# PiLoraGatewayV2_7.net
KiCad netlist of a schematic drawn in EAGLE
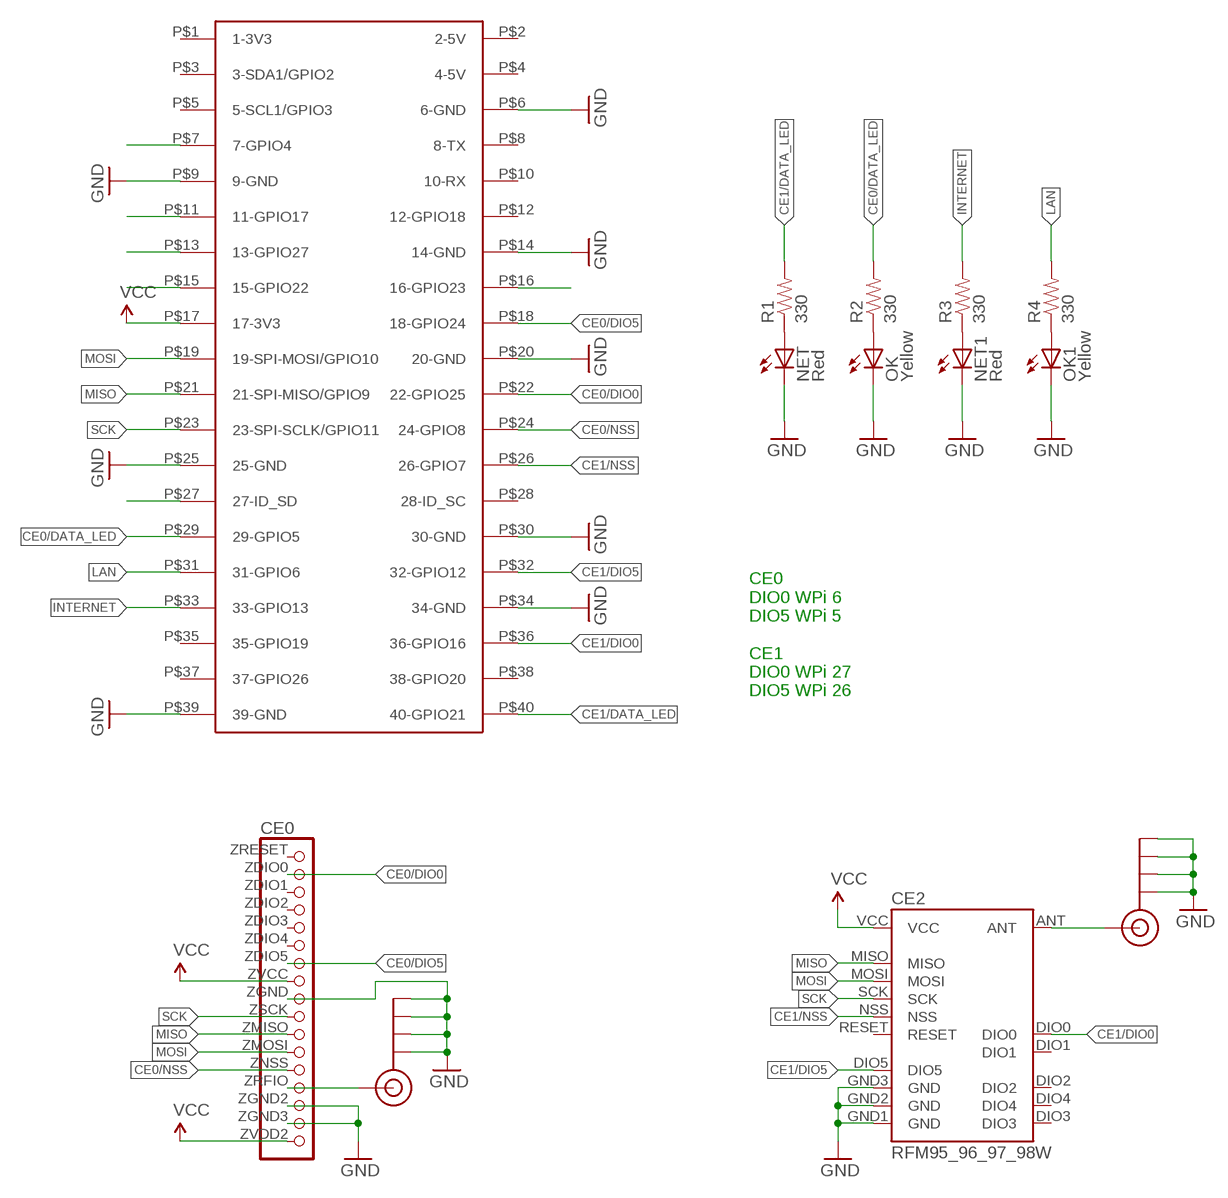
[diagram p0: schematic, sheet 1]

(export (version "E")
  (design (tool "Eeschema 10.0.6"))
  (components
    (comp (ref "CE0")
      (value "DRF1278F_BKOUTDP1276")
      (footprint "eagle-import:ANYLINK_DP1276")
      (libsource (lib "eagle-import") (part "DRF1278F_BKOUTDP1276"))
    )
    (comp (ref "CE2")
      (value "RFM95_96_97_98W")
      (footprint "eagle-import:RFM95_96_97_98W")
      (libsource (lib "eagle-import") (part "RFM95_96_97_98W"))
    )
    (comp (ref "J$1")
      (value "SMA_EDGE")
      (footprint "eagle-import:SMA-EDGE")
      (libsource (lib "eagle-import") (part "SMA_EDGE"))
    )
    (comp (ref "J$2")
      (value "SMA_EDGE")
      (footprint "eagle-import:SMA-EDGE")
      (libsource (lib "eagle-import") (part "SMA_EDGE"))
    )
    (comp (ref "NET")
      (value "Red")
      (footprint "eagle-import:LED-0603")
      (libsource (lib "eagle-import") (part "LED0603"))
    )
    (comp (ref "NET1")
      (value "Red")
      (footprint "eagle-import:LED-0603")
      (libsource (lib "eagle-import") (part "LED0603"))
    )
    (comp (ref "OK")
      (value "Yellow")
      (footprint "eagle-import:LED-0603")
      (libsource (lib "eagle-import") (part "LED0603"))
    )
    (comp (ref "OK1")
      (value "Yellow")
      (footprint "eagle-import:LED-0603")
      (libsource (lib "eagle-import") (part "LED0603"))
    )
    (comp (ref "R1")
      (value "330")
      (footprint "eagle-import:0603-RES")
      (libsource (lib "eagle-import") (part "RESISTOR0603-RES"))
    )
    (comp (ref "R2")
      (value "330")
      (footprint "eagle-import:0603-RES")
      (libsource (lib "eagle-import") (part "RESISTOR0603-RES"))
    )
    (comp (ref "R3")
      (value "330")
      (footprint "eagle-import:0603-RES")
      (libsource (lib "eagle-import") (part "RESISTOR0603-RES"))
    )
    (comp (ref "R4")
      (value "330")
      (footprint "eagle-import:0603-RES")
      (libsource (lib "eagle-import") (part "RESISTOR0603-RES"))
    )
    (comp (ref "U$1")
      (value "RASPBERRY-PI+")
      (footprint "eagle-import:RASPBERRY-PI-PLUS-CAM_NOTCH")
      (libsource (lib "eagle-import") (part "RASPBERRY-PI+"))
    )
  )
  (nets
    (net (code "1") (name "CE0{slash}DATA_LED") (class "Default")
      (node (ref "R2") (pin "2") (pinfunction "2_2") (pintype "passive"))
      (node (ref "U$1") (pin "P$29") (pinfunction "29-GPIO5_P$29") (pintype "bidirectional"))
    )
    (net (code "2") (name "CE0{slash}DIO0") (class "Default")
      (node (ref "CE0") (pin "ZDIO0") (pinfunction "DIO0_ZDIO0") (pintype "passive"))
      (node (ref "U$1") (pin "P$22") (pinfunction "22-GPIO25_P$22") (pintype "bidirectional"))
    )
    (net (code "3") (name "CE0{slash}DIO5") (class "Default")
      (node (ref "CE0") (pin "ZDIO5") (pinfunction "DIO5_ZDIO5") (pintype "passive"))
      (node (ref "U$1") (pin "P$18") (pinfunction "18-GPIO24_P$18") (pintype "bidirectional"))
    )
    (net (code "4") (name "CE0{slash}NSS") (class "Default")
      (node (ref "CE0") (pin "ZNSS") (pinfunction "NSS_ZNSS") (pintype "passive"))
      (node (ref "U$1") (pin "P$24") (pinfunction "24-GPIO8_P$24") (pintype "bidirectional"))
    )
    (net (code "5") (name "CE1{slash}DATA_LED") (class "Default")
      (node (ref "R1") (pin "2") (pinfunction "2_2") (pintype "passive"))
      (node (ref "U$1") (pin "P$40") (pinfunction "40-GPIO21_P$40") (pintype "bidirectional"))
    )
    (net (code "6") (name "CE1{slash}DIO0") (class "Default")
      (node (ref "CE2") (pin "DIO0") (pinfunction "DIO0_DIO0") (pintype "input"))
      (node (ref "U$1") (pin "P$36") (pinfunction "36-GPIO16_P$36") (pintype "bidirectional"))
    )
    (net (code "7") (name "CE1{slash}DIO5") (class "Default")
      (node (ref "CE2") (pin "DIO5") (pinfunction "DIO5_DIO5") (pintype "input"))
      (node (ref "U$1") (pin "P$32") (pinfunction "32-GPIO12_P$32") (pintype "bidirectional"))
    )
    (net (code "8") (name "CE1{slash}NSS") (class "Default")
      (node (ref "CE2") (pin "NSS") (pinfunction "NSS_NSS") (pintype "input"))
      (node (ref "U$1") (pin "P$26") (pinfunction "26-GPIO7_P$26") (pintype "bidirectional"))
    )
    (net (code "9") (name "GND") (class "Default")
      (node (ref "CE0") (pin "ZGND") (pinfunction "GND_ZGND") (pintype "passive"))
      (node (ref "CE0") (pin "ZGND2") (pinfunction "RGND1_ZGND2") (pintype "passive"))
      (node (ref "CE0") (pin "ZGND3") (pinfunction "RGND2_ZGND3") (pintype "passive"))
      (node (ref "CE2") (pin "GND1") (pinfunction "GND_GND1") (pintype "power_in"))
      (node (ref "CE2") (pin "GND2") (pinfunction "GND_GND2") (pintype "power_in"))
      (node (ref "CE2") (pin "GND3") (pinfunction "GND_GND3") (pintype "power_in"))
      (node (ref "J$1") (pin "GND@0") (pinfunction "GND_GND@0") (pintype "bidirectional"))
      (node (ref "J$1") (pin "GND@1") (pinfunction "GND_GND@1") (pintype "bidirectional"))
      (node (ref "J$1") (pin "GND@2") (pinfunction "GND_GND@2") (pintype "bidirectional"))
      (node (ref "J$1") (pin "GND@3") (pinfunction "GND_GND@3") (pintype "bidirectional"))
      (node (ref "J$2") (pin "GND@0") (pinfunction "GND_GND@0") (pintype "bidirectional"))
      (node (ref "J$2") (pin "GND@1") (pinfunction "GND_GND@1") (pintype "bidirectional"))
      (node (ref "J$2") (pin "GND@2") (pinfunction "GND_GND@2") (pintype "bidirectional"))
      (node (ref "J$2") (pin "GND@3") (pinfunction "GND_GND@3") (pintype "bidirectional"))
      (node (ref "NET") (pin "C") (pinfunction "C_C") (pintype "passive"))
      (node (ref "NET1") (pin "C") (pinfunction "C_C") (pintype "passive"))
      (node (ref "OK") (pin "C") (pinfunction "C_C") (pintype "passive"))
      (node (ref "OK1") (pin "C") (pinfunction "C_C") (pintype "passive"))
      (node (ref "U$1") (pin "P$14") (pinfunction "14-GND_P$14") (pintype "bidirectional"))
      (node (ref "U$1") (pin "P$20") (pinfunction "20-GND_P$20") (pintype "bidirectional"))
      (node (ref "U$1") (pin "P$25") (pinfunction "25-GND_P$25") (pintype "bidirectional"))
      (node (ref "U$1") (pin "P$30") (pinfunction "30-GND_P$30") (pintype "bidirectional"))
      (node (ref "U$1") (pin "P$34") (pinfunction "34-GND_P$34") (pintype "bidirectional"))
      (node (ref "U$1") (pin "P$39") (pinfunction "39-GND_P$39") (pintype "bidirectional"))
      (node (ref "U$1") (pin "P$6") (pinfunction "6-GND_P$6") (pintype "bidirectional"))
      (node (ref "U$1") (pin "P$9") (pinfunction "9-GND_P$9") (pintype "bidirectional"))
    )
    (net (code "10") (name "INTERNET") (class "Default")
      (node (ref "R3") (pin "2") (pinfunction "2_2") (pintype "passive"))
      (node (ref "U$1") (pin "P$33") (pinfunction "33-GPIO13_P$33") (pintype "bidirectional"))
    )
    (net (code "11") (name "LAN") (class "Default")
      (node (ref "R4") (pin "2") (pinfunction "2_2") (pintype "passive"))
      (node (ref "U$1") (pin "P$31") (pinfunction "31-GPIO6_P$31") (pintype "bidirectional"))
    )
    (net (code "12") (name "MISO") (class "Default")
      (node (ref "CE0") (pin "ZMISO") (pinfunction "MISO_ZMISO") (pintype "passive"))
      (node (ref "CE2") (pin "MISO") (pinfunction "MISO_MISO") (pintype "output"))
      (node (ref "U$1") (pin "P$21") (pinfunction "21-SPI-MISO/GPIO9_P$21") (pintype "bidirectional"))
    )
    (net (code "13") (name "MOSI") (class "Default")
      (node (ref "CE0") (pin "ZMOSI") (pinfunction "MOSI_ZMOSI") (pintype "passive"))
      (node (ref "CE2") (pin "MOSI") (pinfunction "MOSI_MOSI") (pintype "input"))
      (node (ref "U$1") (pin "P$19") (pinfunction "19-SPI-MOSI/GPIO10_P$19") (pintype "bidirectional"))
    )
    (net (code "14") (name "Net-(CE0-RFIO)") (class "Default")
      (node (ref "CE0") (pin "ZRFIO") (pinfunction "RFIO_ZRFIO") (pintype "passive"))
      (node (ref "J$1") (pin "SIG") (pinfunction "SIGNAL_SIG") (pintype "bidirectional"))
    )
    (net (code "15") (name "Net-(J$2-SIGNAL)") (class "Default")
      (node (ref "CE2") (pin "ANT") (pinfunction "ANT_ANT") (pintype "bidirectional"))
      (node (ref "J$2") (pin "SIG") (pinfunction "SIGNAL_SIG") (pintype "bidirectional"))
    )
    (net (code "16") (name "Net-(NET-PadA)") (class "Default")
      (node (ref "NET") (pin "A") (pinfunction "A_A") (pintype "passive"))
      (node (ref "R1") (pin "1") (pinfunction "1_1") (pintype "passive"))
    )
    (net (code "17") (name "Net-(NET1-PadA)") (class "Default")
      (node (ref "NET1") (pin "A") (pinfunction "A_A") (pintype "passive"))
      (node (ref "R3") (pin "1") (pinfunction "1_1") (pintype "passive"))
    )
    (net (code "18") (name "Net-(OK-PadA)") (class "Default")
      (node (ref "OK") (pin "A") (pinfunction "A_A") (pintype "passive"))
      (node (ref "R2") (pin "1") (pinfunction "1_1") (pintype "passive"))
    )
    (net (code "19") (name "Net-(OK1-PadA)") (class "Default")
      (node (ref "OK1") (pin "A") (pinfunction "A_A") (pintype "passive"))
      (node (ref "R4") (pin "1") (pinfunction "1_1") (pintype "passive"))
    )
    (net (code "20") (name "SCK") (class "Default")
      (node (ref "CE0") (pin "ZSCK") (pinfunction "SCK_ZSCK") (pintype "passive"))
      (node (ref "CE2") (pin "SCK") (pinfunction "SCK_SCK") (pintype "input"))
      (node (ref "U$1") (pin "P$23") (pinfunction "23-SPI-SCLK/GPIO11_P$23") (pintype "bidirectional"))
    )
    (net (code "21") (name "VCC") (class "Default")
      (node (ref "CE0") (pin "ZVCC") (pinfunction "VCC_ZVCC") (pintype "passive"))
      (node (ref "CE0") (pin "ZVDD2") (pinfunction "VCC2_ZVDD2") (pintype "passive"))
      (node (ref "CE2") (pin "VCC") (pinfunction "VCC_VCC") (pintype "bidirectional"))
      (node (ref "U$1") (pin "P$17") (pinfunction "17-3V3_P$17") (pintype "bidirectional"))
    )
    (net (code "22") (name "unconnected-(CE0-DIO1-PadZDIO1)") (class "Default")
      (node (ref "CE0") (pin "ZDIO1") (pinfunction "DIO1_ZDIO1") (pintype "passive"))
    )
    (net (code "23") (name "unconnected-(CE0-DIO2-PadZDIO2)") (class "Default")
      (node (ref "CE0") (pin "ZDIO2") (pinfunction "DIO2_ZDIO2") (pintype "passive"))
    )
    (net (code "24") (name "unconnected-(CE0-DIO3-PadZDIO3)") (class "Default")
      (node (ref "CE0") (pin "ZDIO3") (pinfunction "DIO3_ZDIO3") (pintype "passive"))
    )
    (net (code "25") (name "unconnected-(CE0-DIO4-PadZDIO4)") (class "Default")
      (node (ref "CE0") (pin "ZDIO4") (pinfunction "DIO4_ZDIO4") (pintype "passive"))
    )
    (net (code "26") (name "unconnected-(CE0-RESET-PadZRESET)") (class "Default")
      (node (ref "CE0") (pin "ZRESET") (pinfunction "RESET_ZRESET") (pintype "passive"))
    )
    (net (code "27") (name "unconnected-(CE2-PadDIO1)") (class "Default")
      (node (ref "CE2") (pin "DIO1") (pinfunction "DIO1_DIO1") (pintype "input"))
    )
    (net (code "28") (name "unconnected-(CE2-PadDIO2)") (class "Default")
      (node (ref "CE2") (pin "DIO2") (pinfunction "DIO2_DIO2") (pintype "bidirectional"))
    )
    (net (code "29") (name "unconnected-(CE2-PadDIO3)") (class "Default")
      (node (ref "CE2") (pin "DIO3") (pinfunction "DIO3_DIO3") (pintype "bidirectional"))
    )
    (net (code "30") (name "unconnected-(CE2-PadDIO4)") (class "Default")
      (node (ref "CE2") (pin "DIO4") (pinfunction "DIO4_DIO4") (pintype "bidirectional"))
    )
    (net (code "31") (name "unconnected-(CE2-PadRESET)") (class "Default")
      (node (ref "CE2") (pin "RESET") (pinfunction "RESET_RESET") (pintype "output"))
    )
    (net (code "32") (name "unconnected-(U$1-1-3V3-PadP$1)") (class "Default")
      (node (ref "U$1") (pin "P$1") (pinfunction "1-3V3_P$1") (pintype "bidirectional"))
    )
    (net (code "33") (name "unconnected-(U$1-2-5V-PadP$2)") (class "Default")
      (node (ref "U$1") (pin "P$2") (pinfunction "2-5V_P$2") (pintype "bidirectional"))
    )
    (net (code "34") (name "unconnected-(U$1-3-SDA1{slash}GPIO2-PadP$3)") (class "Default")
      (node (ref "U$1") (pin "P$3") (pinfunction "3-SDA1/GPIO2_P$3") (pintype "bidirectional"))
    )
    (net (code "35") (name "unconnected-(U$1-4-5V-PadP$4)") (class "Default")
      (node (ref "U$1") (pin "P$4") (pinfunction "4-5V_P$4") (pintype "bidirectional"))
    )
    (net (code "36") (name "unconnected-(U$1-5-SCL1{slash}GPIO3-PadP$5)") (class "Default")
      (node (ref "U$1") (pin "P$5") (pinfunction "5-SCL1/GPIO3_P$5") (pintype "bidirectional"))
    )
    (net (code "37") (name "unconnected-(U$1-7-GPIO4-PadP$7)") (class "Default")
      (node (ref "U$1") (pin "P$7") (pinfunction "7-GPIO4_P$7") (pintype "bidirectional"))
    )
    (net (code "38") (name "unconnected-(U$1-8-TX-PadP$8)") (class "Default")
      (node (ref "U$1") (pin "P$8") (pinfunction "8-TX_P$8") (pintype "bidirectional"))
    )
    (net (code "39") (name "unconnected-(U$1-10-RX-PadP$10)") (class "Default")
      (node (ref "U$1") (pin "P$10") (pinfunction "10-RX_P$10") (pintype "bidirectional"))
    )
    (net (code "40") (name "unconnected-(U$1-11-GPIO17-PadP$11)") (class "Default")
      (node (ref "U$1") (pin "P$11") (pinfunction "11-GPIO17_P$11") (pintype "bidirectional"))
    )
    (net (code "41") (name "unconnected-(U$1-12-GPIO18-PadP$12)") (class "Default")
      (node (ref "U$1") (pin "P$12") (pinfunction "12-GPIO18_P$12") (pintype "bidirectional"))
    )
    (net (code "42") (name "unconnected-(U$1-13-GPIO27-PadP$13)") (class "Default")
      (node (ref "U$1") (pin "P$13") (pinfunction "13-GPIO27_P$13") (pintype "bidirectional"))
    )
    (net (code "43") (name "unconnected-(U$1-15-GPIO22-PadP$15)") (class "Default")
      (node (ref "U$1") (pin "P$15") (pinfunction "15-GPIO22_P$15") (pintype "bidirectional"))
    )
    (net (code "44") (name "unconnected-(U$1-16-GPIO23-PadP$16)") (class "Default")
      (node (ref "U$1") (pin "P$16") (pinfunction "16-GPIO23_P$16") (pintype "bidirectional"))
    )
    (net (code "45") (name "unconnected-(U$1-27-ID_SD-PadP$27)") (class "Default")
      (node (ref "U$1") (pin "P$27") (pinfunction "27-ID_SD_P$27") (pintype "bidirectional"))
    )
    (net (code "46") (name "unconnected-(U$1-28-ID_SC-PadP$28)") (class "Default")
      (node (ref "U$1") (pin "P$28") (pinfunction "28-ID_SC_P$28") (pintype "bidirectional"))
    )
    (net (code "47") (name "unconnected-(U$1-35-GPIO19-PadP$35)") (class "Default")
      (node (ref "U$1") (pin "P$35") (pinfunction "35-GPIO19_P$35") (pintype "bidirectional"))
    )
    (net (code "48") (name "unconnected-(U$1-37-GPIO26-PadP$37)") (class "Default")
      (node (ref "U$1") (pin "P$37") (pinfunction "37-GPIO26_P$37") (pintype "bidirectional"))
    )
    (net (code "49") (name "unconnected-(U$1-38-GPIO20-PadP$38)") (class "Default")
      (node (ref "U$1") (pin "P$38") (pinfunction "38-GPIO20_P$38") (pintype "bidirectional"))
    )
  )
)
